# fet-dd-charger-20mm-mk-1_1-bottom.net
KiCad netlist of a schematic drawn in EAGLE
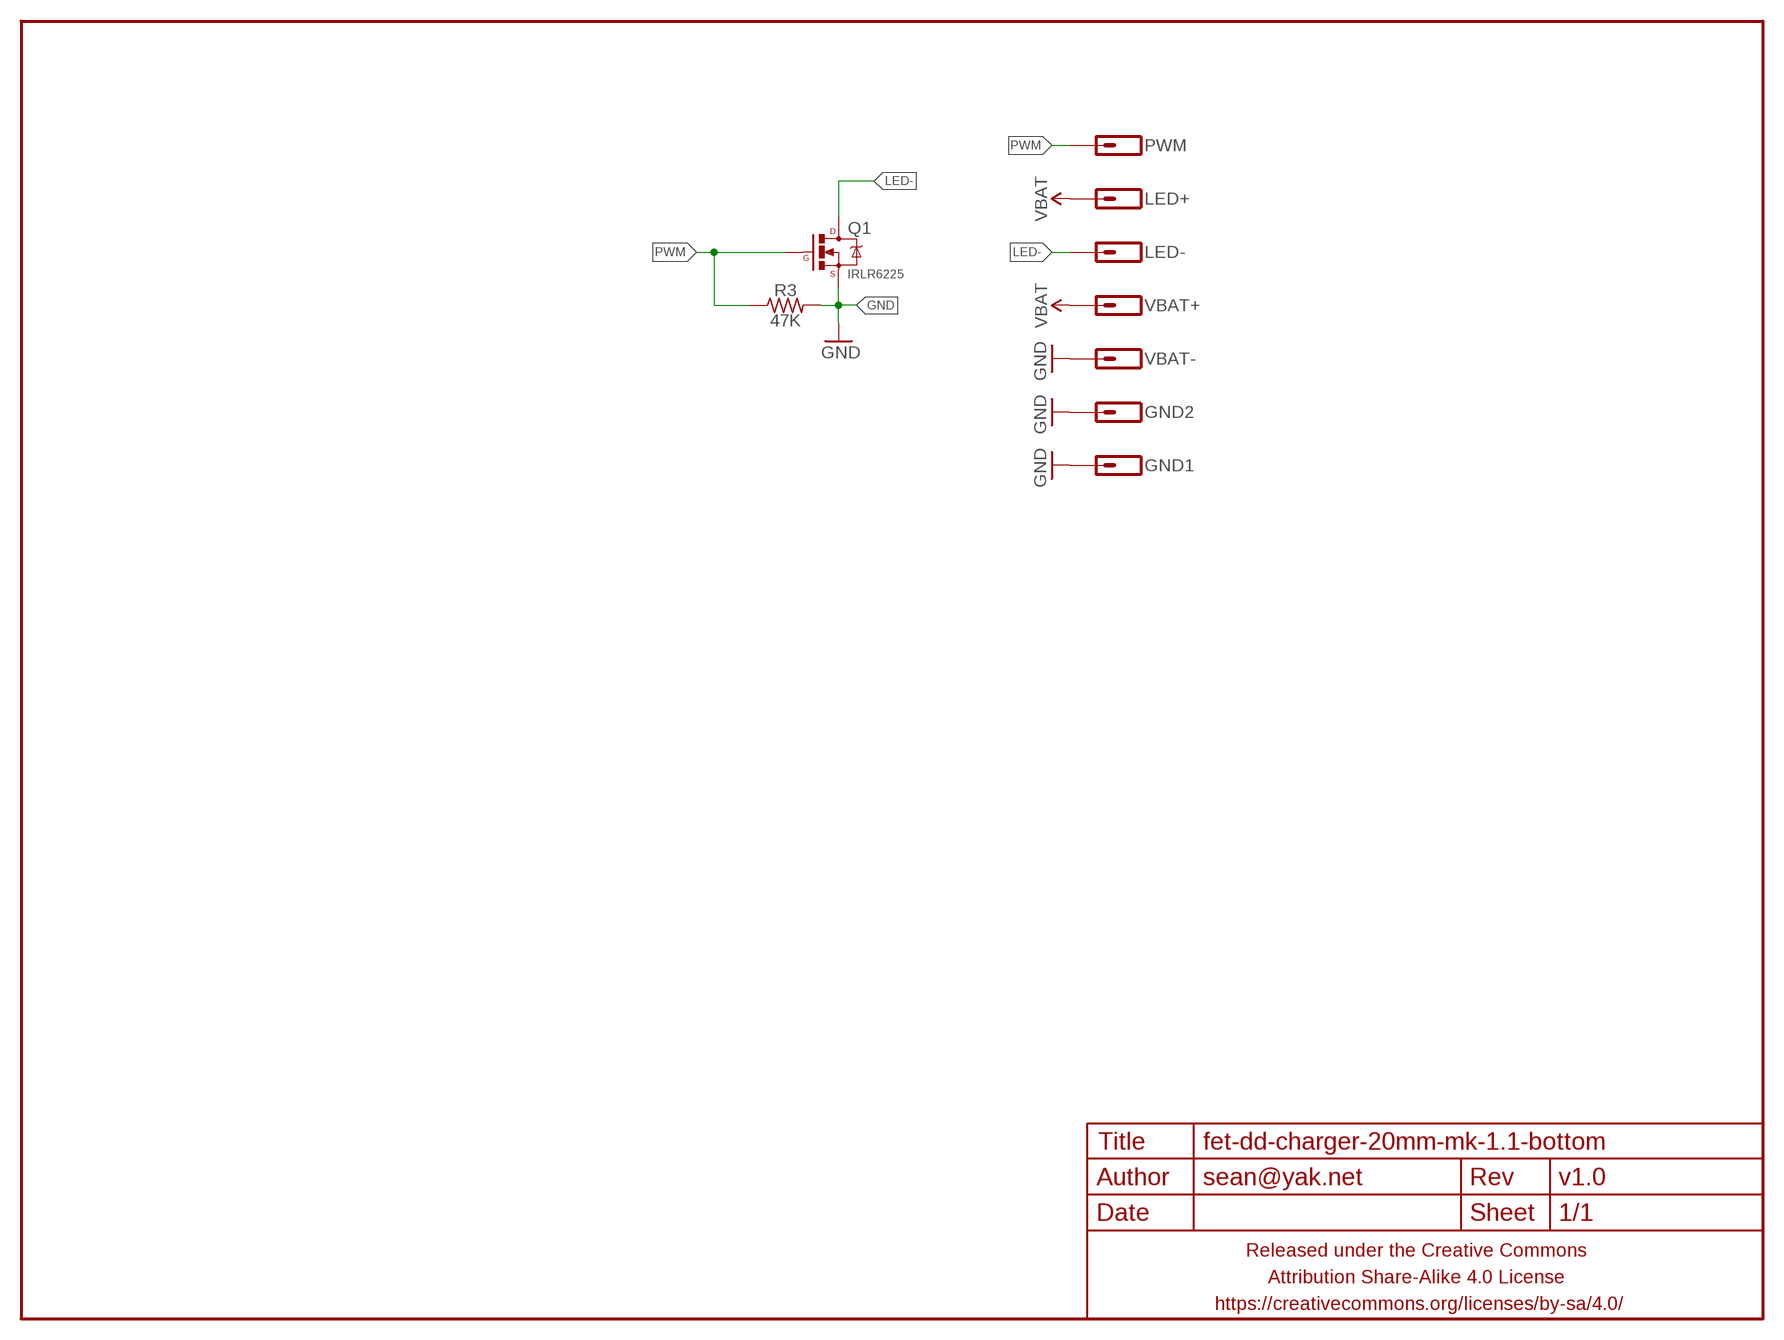
[diagram p0: schematic, sheet 1]

(export (version "E")
  (design (tool "Eeschema 10.0.6"))
  (components
    (comp (ref "FRAME1")
      (value "FRAME-LETTERNO_PACKAGE")
      (footprint "eagle-import:DUMMY")
      (fields (field (name "DESIGNER") "sean@yak.net") (field (name "VERSION") "v1.0"))
      (libsource (lib "eagle-import") (part "FRAME-LETTERNO_PACKAGE"))
    )
    (comp (ref "GND1")
      (value "M01PTH_2MM")
      (footprint "eagle-import:1X01_2MM")
      (libsource (lib "eagle-import") (part "M01PTH_2MM"))
    )
    (comp (ref "GND2")
      (value "M01PTH_2MM")
      (footprint "eagle-import:1X01_2MM")
      (libsource (lib "eagle-import") (part "M01PTH_2MM"))
    )
    (comp (ref "LED+")
      (value "M01PTH_2MM")
      (footprint "eagle-import:1X01_2MM")
      (libsource (lib "eagle-import") (part "M01PTH_2MM"))
    )
    (comp (ref "LED-")
      (value "M01PTH_2MM")
      (footprint "eagle-import:1X01_2MM")
      (libsource (lib "eagle-import") (part "M01PTH_2MM"))
    )
    (comp (ref "PWM")
      (value "M01SMD-1MM-CIR")
      (footprint "eagle-import:1X01-SMD-1MM-DIA")
      (libsource (lib "eagle-import") (part "M01SMD-1MM-CIR"))
    )
    (comp (ref "Q1")
      (value "IRLR6225")
      (footprint "eagle-import:SOT223-CLOSER")
      (libsource (lib "eagle-import") (part "MOSFET-NCHANNELSOT-223-CLOSER"))
    )
    (comp (ref "R3")
      (value "47K")
      (footprint "eagle-import:R0603-TIGHTER")
      (libsource (lib "eagle-import") (part "RESISTORR0603-TIGHTER"))
    )
    (comp (ref "VBAT+")
      (value "M01NOSTOP-CANTSTOP-DONTKNOWHOWTOSTOP")
      (footprint "eagle-import:1X01_SMD_NOSTOP_NOSILK")
      (libsource (lib "eagle-import") (part "M01NOSTOP-CANTSTOP-DONTKNOWHOWTOSTOP"))
    )
    (comp (ref "VBAT-")
      (value "M01NOT-A-VIA-NOPE")
      (footprint "eagle-import:1X01_NOSILK_NOSTOP")
      (libsource (lib "eagle-import") (part "M01NOT-A-VIA-NOPE"))
    )
  )
  (nets
    (net (code "1") (name "GND") (class "Default")
      (node (ref "GND1") (pin "1") (pinfunction "1_1") (pintype "passive"))
      (node (ref "GND2") (pin "1") (pinfunction "1_1") (pintype "passive"))
      (node (ref "Q1") (pin "3") (pinfunction "S_3") (pintype "passive"))
      (node (ref "R3") (pin "2") (pinfunction "2_2") (pintype "passive"))
      (node (ref "VBAT-") (pin "P$1") (pinfunction "1_P$1") (pintype "passive"))
    )
    (net (code "2") (name "LED-") (class "Default")
      (node (ref "LED-") (pin "1") (pinfunction "1_1") (pintype "passive"))
      (node (ref "Q1") (pin "2") (pinfunction "D_2") (pintype "passive"))
      (node (ref "Q1") (pin "4") (pinfunction "D_4") (pintype "passive"))
    )
    (net (code "3") (name "PWM") (class "Default")
      (node (ref "PWM") (pin "P$1") (pinfunction "1_P$1") (pintype "passive"))
      (node (ref "Q1") (pin "1") (pinfunction "G_1") (pintype "passive"))
      (node (ref "R3") (pin "1") (pinfunction "1_1") (pintype "passive"))
    )
    (net (code "4") (name "VBAT") (class "Default")
      (node (ref "LED+") (pin "1") (pinfunction "1_1") (pintype "passive"))
      (node (ref "VBAT+") (pin "1") (pinfunction "1_1") (pintype "passive"))
    )
  )
)
